# Environmental_Sensor.net
KiCad netlist of a schematic drawn in Altium Designer
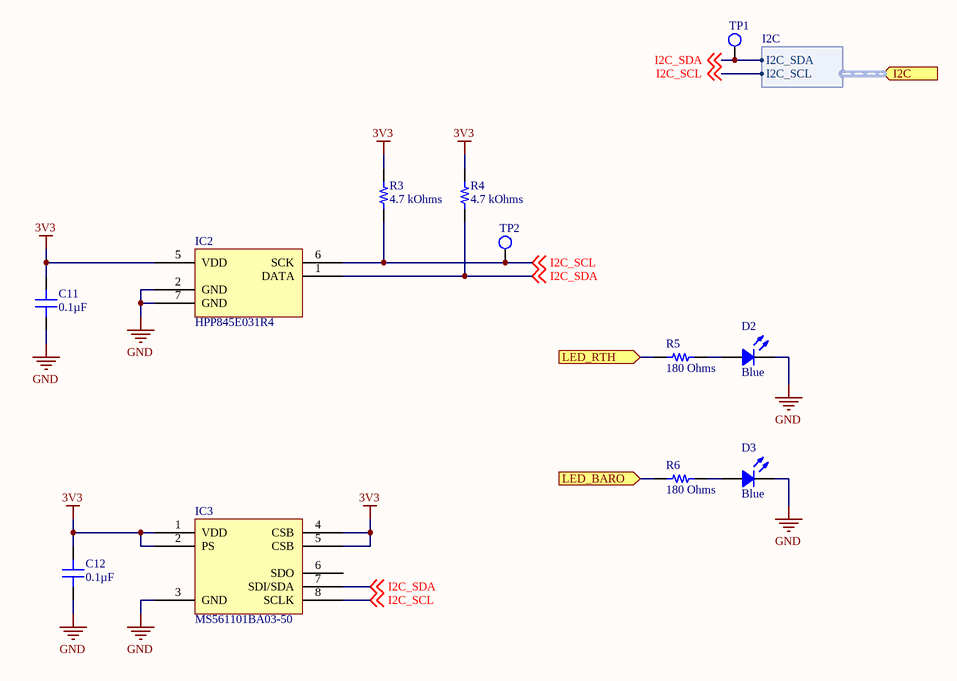
[diagram p0: Environmental Sensor.SchDoc]

(export (version "E")
  (design (tool "Eeschema 10.0.6"))
  (components
    (comp (ref "C11")
      (value "0.1µF")
      (footprint "CAP 0603_1608")
      (description "CAP CER 0.1UF 50V X7R 0603")
      (fields (field (name "PART NUMBER") "06035C104JAT4A") (field (name "MANUFACTURER") "AVX Corporation"))
      (libsource (lib "altiumlibrary.com") (part "Capacitor"))
    )
    (comp (ref "C12")
      (value "0.1µF")
      (footprint "CAP 0603_1608")
      (description "CAP CER 0.1UF 50V X7R 0603")
      (fields (field (name "PART NUMBER") "06035C104JAT4A") (field (name "MANUFACTURER") "AVX Corporation"))
      (libsource (lib "altiumlibrary.com") (part "Capacitor"))
    )
    (comp (ref "D2")
      (value "Blue")
      (footprint "LED 1206_3216 BLUE")
      (description "1206 0.5MM BLUE WATER CLEAR SMT")
      (fields
        (field (name "PART NUMBER") "BL-HB333Q-AV-TRB")
        (field (name "MANUFACTURER") "American Bright Optoelectronics Corporation")
      )
      (libsource (lib "altiumlibrary.com") (part "LED"))
    )
    (comp (ref "D3")
      (value "Blue")
      (footprint "LED 1206_3216 BLUE")
      (description "1206 0.5MM BLUE WATER CLEAR SMT")
      (fields
        (field (name "PART NUMBER") "BL-HB333Q-AV-TRB")
        (field (name "MANUFACTURER") "American Bright Optoelectronics Corporation")
      )
      (libsource (lib "altiumlibrary.com") (part "LED"))
    )
    (comp (ref "IC2")
      (value "HPP845E031R4")
      (footprint "TE HPP845E031R4")
      (description "SENSOR HUMID/TEMP 3V I2C 2% SMD")
      (fields (field (name "MANUFACTURER") "TE Connectivity Measurement Specialties"))
      (libsource (lib "altiumlibrary.com") (part "TE HPP845E031R4"))
    )
    (comp (ref "IC3")
      (value "MS561101BA03-50")
      (footprint "MEAS SPEC MS5611-01BA03")
      (description "BAROMETRIC PRESSURE SENSOR")
      (fields (field (name "MANUFACTURER") "TE Connectivity Measurement Specialties"))
      (libsource (lib "altiumlibrary.com") (part "MEAS SPEC MS5611"))
    )
    (comp (ref "R3")
      (value "4.7 kOhms")
      (footprint "RES 0603_1608")
      (description "RES SMD 4.7K OHM 1% 1/10W 0603")
      (fields
        (field (name "PART NUMBER") "ERJ-3EKF4701V")
        (field (name "MANUFACTURER") "Panasonic Electronic Components")
      )
      (libsource (lib "altiumlibrary.com") (part "Resistor"))
    )
    (comp (ref "R4")
      (value "4.7 kOhms")
      (footprint "RES 0603_1608")
      (description "RES SMD 4.7K OHM 1% 1/10W 0603")
      (fields
        (field (name "PART NUMBER") "ERJ-3EKF4701V")
        (field (name "MANUFACTURER") "Panasonic Electronic Components")
      )
      (libsource (lib "altiumlibrary.com") (part "Resistor"))
    )
    (comp (ref "R5")
      (value "180 Ohms")
      (footprint "RES 0603_1608")
      (description "RES SMD 180 OHM 5% 1/4W 0603")
      (fields
        (field (name "PART NUMBER") "ERJ-PA3J181V")
        (field (name "MANUFACTURER") "Panasonic Electronic Components")
      )
      (libsource (lib "altiumlibrary.com") (part "Resistor"))
    )
    (comp (ref "R6")
      (value "180 Ohms")
      (footprint "RES 0603_1608")
      (description "RES SMD 180 OHM 5% 1/4W 0603")
      (fields
        (field (name "PART NUMBER") "ERJ-PA3J181V")
        (field (name "MANUFACTURER") "Panasonic Electronic Components")
      )
      (libsource (lib "altiumlibrary.com") (part "Resistor"))
    )
    (comp (ref "TP1")
      (value "Test Point")
      (footprint "TestPoint-1.5mm")
      (libsource (lib "CelestialUseful") (part "Test Point"))
    )
    (comp (ref "TP2")
      (value "Test Point")
      (footprint "TestPoint-1.5mm")
      (libsource (lib "CelestialUseful") (part "Test Point"))
    )
  )
  (nets
    (net (code "2") (name "/LED_BARO") (class "Default")
      (node (ref "R6") (pin "1") (pinfunction "1_1") (pintype "passive"))
    )
    (net (code "3") (name "/LED_RTH") (class "Default")
      (node (ref "R5") (pin "1") (pinfunction "1_1") (pintype "passive"))
    )
    (net (code "5") (name "3V3") (class "Default")
      (node (ref "C11") (pin "2") (pinfunction "2_2") (pintype "passive"))
      (node (ref "C12") (pin "2") (pinfunction "2_2") (pintype "passive"))
      (node (ref "IC2") (pin "5") (pinfunction "VDD_5") (pintype "passive"))
      (node (ref "IC3") (pin "1") (pinfunction "VDD_1") (pintype "passive"))
      (node (ref "IC3") (pin "2") (pinfunction "PS_2") (pintype "passive"))
      (node (ref "IC3") (pin "4") (pinfunction "CSB_4") (pintype "passive"))
      (node (ref "IC3") (pin "5") (pinfunction "CSB_5") (pintype "passive"))
      (node (ref "R3") (pin "2") (pinfunction "2_2") (pintype "passive"))
      (node (ref "R4") (pin "2") (pinfunction "2_2") (pintype "passive"))
    )
    (net (code "6") (name "GND") (class "Default")
      (node (ref "C11") (pin "1") (pinfunction "1_1") (pintype "passive"))
      (node (ref "C12") (pin "1") (pinfunction "1_1") (pintype "passive"))
      (node (ref "D2") (pin "2") (pinfunction "2_2") (pintype "passive"))
      (node (ref "D3") (pin "2") (pinfunction "2_2") (pintype "passive"))
      (node (ref "IC2") (pin "2") (pinfunction "GND_2") (pintype "passive"))
      (node (ref "IC2") (pin "7") (pinfunction "GND_7") (pintype "passive"))
      (node (ref "IC3") (pin "3") (pinfunction "GND_3") (pintype "passive"))
    )
    (net (code "7") (name "I2C_SCL") (class "Default")
      (node (ref "IC2") (pin "6") (pinfunction "SCK_6") (pintype "passive"))
      (node (ref "IC3") (pin "8") (pinfunction "SCLK_8") (pintype "passive"))
      (node (ref "R3") (pin "1") (pinfunction "1_1") (pintype "passive"))
      (node (ref "TP2") (pin "1") (pinfunction "TP_1") (pintype "passive"))
    )
    (net (code "8") (name "I2C_SDA") (class "Default")
      (node (ref "IC2") (pin "1") (pinfunction "DATA_1") (pintype "passive"))
      (node (ref "IC3") (pin "7") (pinfunction "SDI/SDA_7") (pintype "passive"))
      (node (ref "R4") (pin "1") (pinfunction "1_1") (pintype "passive"))
      (node (ref "TP1") (pin "1") (pinfunction "TP_1") (pintype "passive"))
    )
    (net (code "9") (name "Net-(D2-Pad1)") (class "Default")
      (node (ref "D2") (pin "1") (pinfunction "1_1") (pintype "passive"))
      (node (ref "R5") (pin "2") (pinfunction "2_2") (pintype "passive"))
    )
    (net (code "10") (name "Net-(D3-Pad1)") (class "Default")
      (node (ref "D3") (pin "1") (pinfunction "1_1") (pintype "passive"))
      (node (ref "R6") (pin "2") (pinfunction "2_2") (pintype "passive"))
    )
    (net (code "11") (name "unconnected-(IC3-SDO-Pad6)") (class "Default")
      (node (ref "IC3") (pin "6") (pinfunction "SDO_6") (pintype "passive"))
    )
  )
)
